# coil-control-module-v1.net
KiCad netlist of a schematic drawn in EAGLE
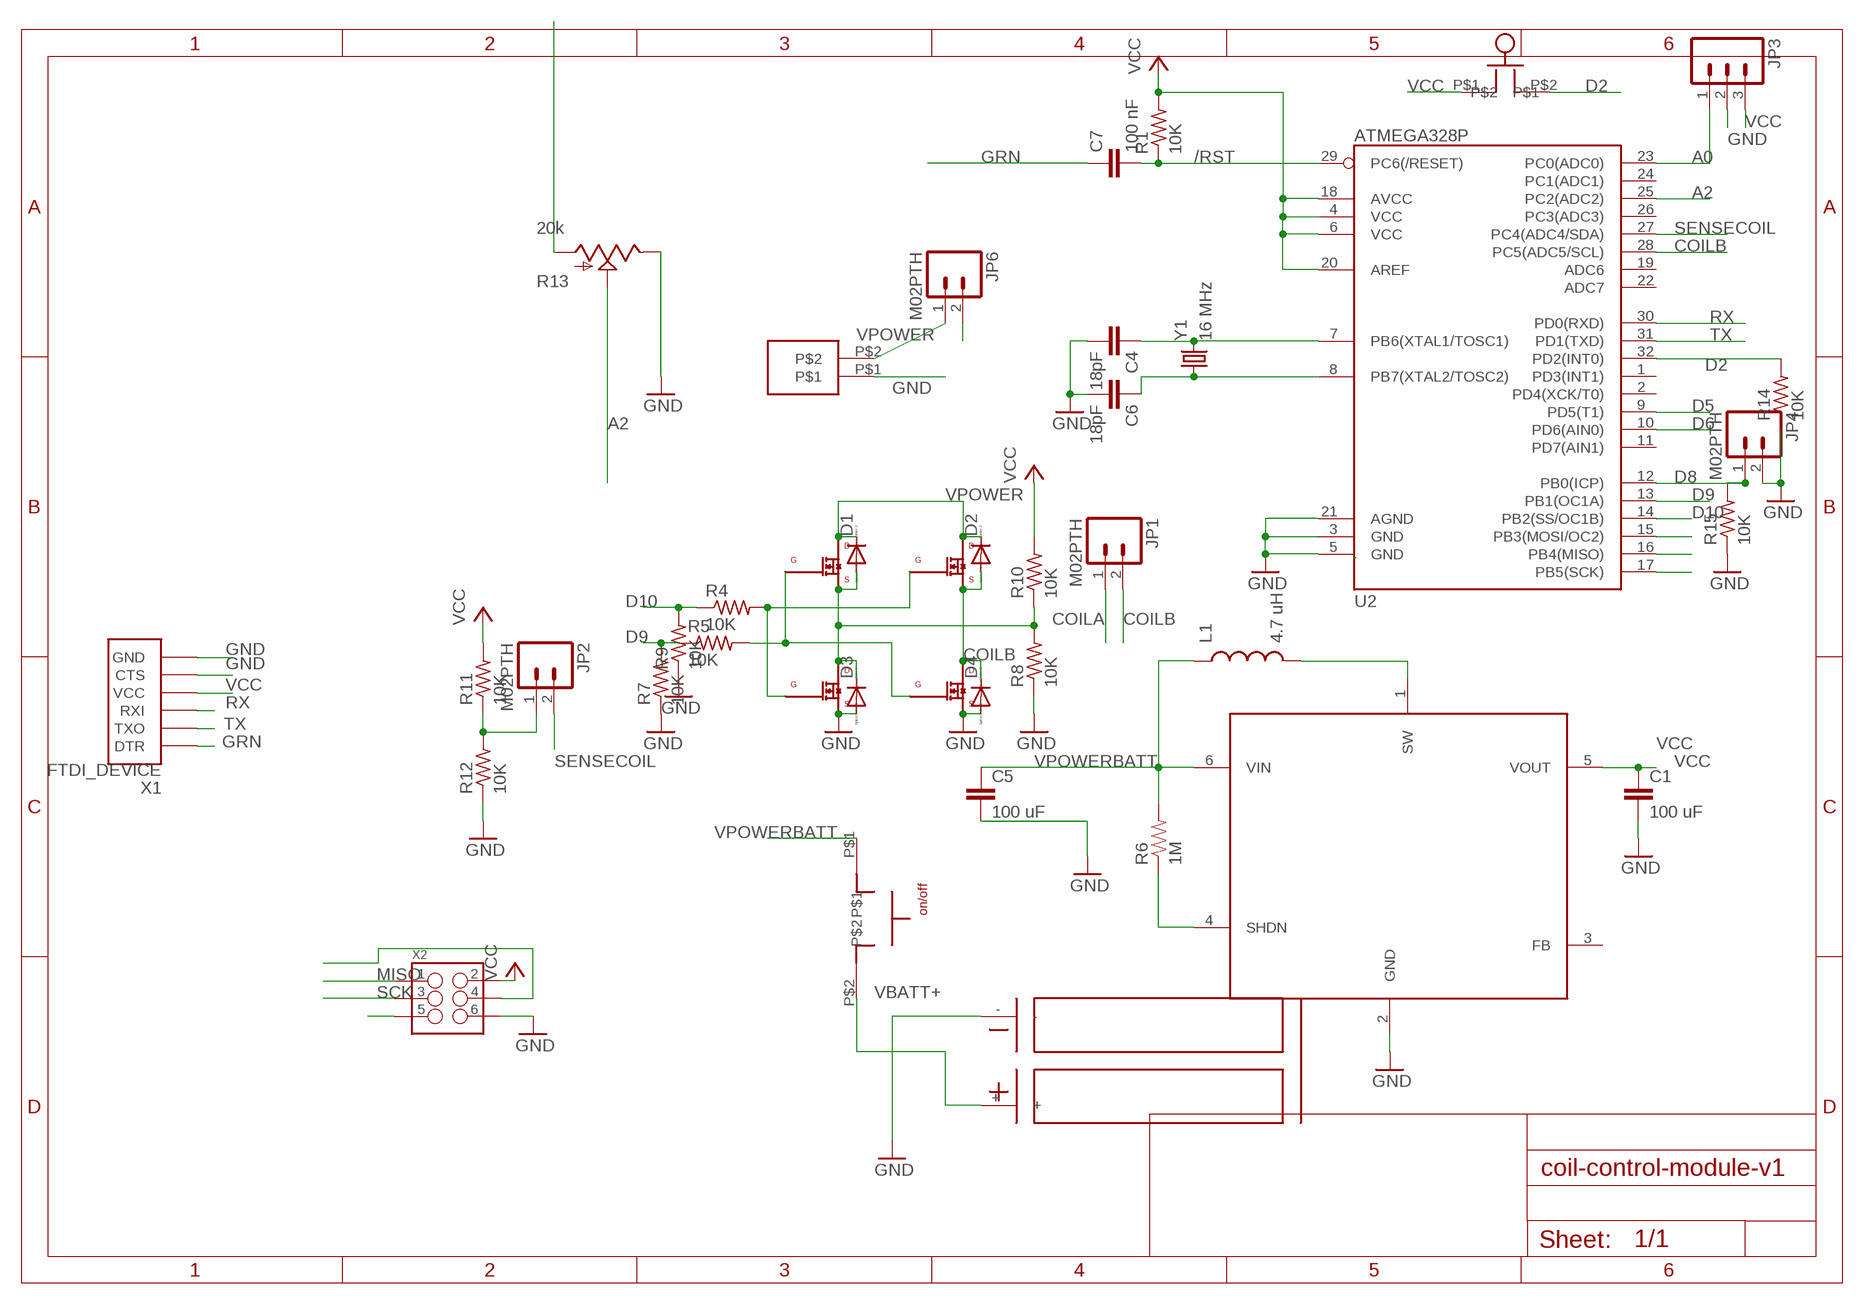
[diagram p0: schematic, sheet 1]

(export (version "E")
  (design (tool "Eeschema 10.0.6"))
  (components
    (comp (ref "C1")
      (value "100 uF")
      (footprint "eagle-import:1206")
      (libsource (lib "eagle-import") (part "CAP1206"))
    )
    (comp (ref "C4")
      (value "18pF")
      (footprint "eagle-import:C0603")
      (libsource (lib "eagle-import") (part "C-EUC0603"))
    )
    (comp (ref "C5")
      (value "100 uF")
      (footprint "eagle-import:1206")
      (libsource (lib "eagle-import") (part "CAP1206"))
    )
    (comp (ref "C6")
      (value "18pF")
      (footprint "eagle-import:C0603")
      (libsource (lib "eagle-import") (part "C-EUC0603"))
    )
    (comp (ref "C7")
      (value "100 nF")
      (footprint "eagle-import:0603-CAP")
      (libsource (lib "eagle-import") (part "SparkFun-Passives_CAP0603-CAP"))
    )
    (comp (ref "D1")
      (value "DIODE-DO-214AC")
      (footprint "eagle-import:DO-214AC")
      (libsource (lib "eagle-import") (part "DIODE-DO-214AC"))
    )
    (comp (ref "D2")
      (value "DIODE-DO-214AC")
      (footprint "eagle-import:DO-214AC")
      (libsource (lib "eagle-import") (part "DIODE-DO-214AC"))
    )
    (comp (ref "D3")
      (value "DIODE-DO-214AC")
      (footprint "eagle-import:DO-214AC")
      (libsource (lib "eagle-import") (part "DIODE-DO-214AC"))
    )
    (comp (ref "D4")
      (value "DIODE-DO-214AC")
      (footprint "eagle-import:DO-214AC")
      (libsource (lib "eagle-import") (part "DIODE-DO-214AC"))
    )
    (comp (ref "JP1")
      (value "M02PTH")
      (footprint "eagle-import:1X02")
      (libsource (lib "eagle-import") (part "M02PTH"))
    )
    (comp (ref "JP2")
      (value "M02PTH")
      (footprint "eagle-import:1X02")
      (libsource (lib "eagle-import") (part "M02PTH"))
    )
    (comp (ref "JP3")
      (value "M03PTH")
      (footprint "eagle-import:1X03")
      (libsource (lib "eagle-import") (part "M03PTH"))
    )
    (comp (ref "JP4")
      (value "M02PTH")
      (footprint "eagle-import:1X02")
      (libsource (lib "eagle-import") (part "M02PTH"))
    )
    (comp (ref "JP6")
      (value "M02PTH")
      (footprint "eagle-import:1X02")
      (libsource (lib "eagle-import") (part "M02PTH"))
    )
    (comp (ref "L1")
      (value "4.7 uH")
      (footprint "eagle-import:0805")
      (libsource (lib "eagle-import") (part "INDUCTOR0805"))
    )
    (comp (ref "R1")
      (value "10K")
      (footprint "eagle-import:R0603")
      (libsource (lib "eagle-import") (part "R-US_R0603"))
    )
    (comp (ref "R4")
      (value "10K")
      (footprint "eagle-import:R0603")
      (libsource (lib "eagle-import") (part "R-US_R0603"))
    )
    (comp (ref "R5")
      (value "10K")
      (footprint "eagle-import:R0603")
      (libsource (lib "eagle-import") (part "R-US_R0603"))
    )
    (comp (ref "R6")
      (value "1M")
      (footprint "eagle-import:0805")
      (libsource (lib "eagle-import") (part "RESISTOR0805-RES"))
    )
    (comp (ref "R7")
      (value "10K")
      (footprint "eagle-import:R0603")
      (libsource (lib "eagle-import") (part "R-US_R0603"))
    )
    (comp (ref "R8")
      (value "10K")
      (footprint "eagle-import:R0603")
      (libsource (lib "eagle-import") (part "R-US_R0603"))
    )
    (comp (ref "R9")
      (value "10K")
      (footprint "eagle-import:R0603")
      (libsource (lib "eagle-import") (part "R-US_R0603"))
    )
    (comp (ref "R10")
      (value "10K")
      (footprint "eagle-import:R0603")
      (libsource (lib "eagle-import") (part "R-US_R0603"))
    )
    (comp (ref "R11")
      (value "10K")
      (footprint "eagle-import:R0603")
      (libsource (lib "eagle-import") (part "R-US_R0603"))
    )
    (comp (ref "R12")
      (value "10K")
      (footprint "eagle-import:R0603")
      (libsource (lib "eagle-import") (part "R-US_R0603"))
    )
    (comp (ref "R13")
      (value "20k")
      (footprint "eagle-import:ALPS_POT_KIT")
      (libsource (lib "eagle-import") (part "POTALPS-KIT"))
    )
    (comp (ref "R14")
      (value "10K")
      (footprint "eagle-import:R0603")
      (libsource (lib "eagle-import") (part "R-US_R0603"))
    )
    (comp (ref "R15")
      (value "10K")
      (footprint "eagle-import:R0603")
      (libsource (lib "eagle-import") (part "R-US_R0603"))
    )
    (comp (ref "U$1")
      (value "IRLML0060")
      (footprint "eagle-import:SOT-23")
      (libsource (lib "eagle-import") (part "IRLML0060"))
    )
    (comp (ref "U$2")
      (value "IRLML0060")
      (footprint "eagle-import:SOT-23")
      (libsource (lib "eagle-import") (part "IRLML0060"))
    )
    (comp (ref "U$3")
      (value "IRLML0060")
      (footprint "eagle-import:SOT-23")
      (libsource (lib "eagle-import") (part "IRLML0060"))
    )
    (comp (ref "U$4")
      (value "AA-DOUBLE-UPSIDE-DOWN")
      (footprint "eagle-import:AA-DOUBLE-UPSIDE-DOWN")
      (libsource (lib "eagle-import") (part "AA-DOUBLE-UPSIDE-DOWN"))
    )
    (comp (ref "U$5")
      (value "CW182-ND")
      (footprint "eagle-import:CW182-ND")
      (libsource (lib "eagle-import") (part "CW182-ND"))
    )
    (comp (ref "U$6")
      (value "IRLML0060")
      (footprint "eagle-import:SOT-23")
      (libsource (lib "eagle-import") (part "IRLML0060"))
    )
    (comp (ref "U$7")
      (value "BUTTON")
      (footprint "eagle-import:BUTTON")
      (libsource (lib "eagle-import") (part "BUTTON"))
    )
    (comp (ref "U$8")
      (value "SPRING-TERMINAL")
      (footprint "eagle-import:SPRING-TERMINAL")
      (libsource (lib "eagle-import") (part "SPRING-TERMINAL"))
    )
    (comp (ref "U1")
      (value "AAT1217")
      (footprint "eagle-import:SSOT23-6")
      (libsource (lib "eagle-import") (part "AAT1217"))
    )
    (comp (ref "U2")
      (value "ATMEGA328P")
      (footprint "eagle-import:TQFP32-08")
      (libsource (lib "eagle-import") (part "ATMEGA328_SMT"))
    )
    (comp (ref "X1")
      (value "FTDI_DEVICE")
      (footprint "eagle-import:FTDI_DEVICE_SIDE")
      (libsource (lib "eagle-import") (part "FTDI_DEVICE"))
    )
    (comp (ref "X2")
      (value "M03X2NO_SILK")
      (footprint "eagle-import:2X3-NS")
      (libsource (lib "eagle-import") (part "M03X2NO_SILK"))
    )
    (comp (ref "Y1")
      (value "16 MHz")
      (footprint "eagle-import:CRYSTAL-SMD-5X3")
      (libsource (lib "eagle-import") (part "CRYSTAL5X3"))
    )
  )
  (nets
    (net (code "1") (name "/A0") (class "Default")
      (node (ref "JP3") (pin "1") (pinfunction "1_1") (pintype "passive"))
      (node (ref "U2") (pin "23") (pinfunction "PC0(ADC0)_23") (pintype "bidirectional"))
    )
    (net (code "2") (name "/A2") (class "Default")
      (node (ref "R13") (pin "P$2") (pinfunction "S_P$2") (pintype "passive"))
      (node (ref "U2") (pin "25") (pinfunction "PC2(ADC2)_25") (pintype "bidirectional"))
    )
    (net (code "3") (name "/COILA") (class "Default")
      (node (ref "D1") (pin "A") (pinfunction "A_A") (pintype "passive"))
      (node (ref "D3") (pin "C") (pinfunction "C_C") (pintype "passive"))
      (node (ref "JP1") (pin "1") (pinfunction "1_1") (pintype "passive"))
      (node (ref "R10") (pin "1") (pinfunction "1_1") (pintype "passive"))
      (node (ref "R8") (pin "2") (pinfunction "2_2") (pintype "passive"))
      (node (ref "U$3") (pin "2") (pinfunction "SOURCE_2") (pintype "bidirectional"))
      (node (ref "U$6") (pin "3") (pinfunction "DRAIN_3") (pintype "bidirectional"))
    )
    (net (code "4") (name "/COILB") (class "Default")
      (node (ref "D2") (pin "A") (pinfunction "A_A") (pintype "passive"))
      (node (ref "D4") (pin "C") (pinfunction "C_C") (pintype "passive"))
      (node (ref "JP1") (pin "2") (pinfunction "2_2") (pintype "passive"))
      (node (ref "U$1") (pin "3") (pinfunction "DRAIN_3") (pintype "bidirectional"))
      (node (ref "U$2") (pin "2") (pinfunction "SOURCE_2") (pintype "bidirectional"))
      (node (ref "U2") (pin "28") (pinfunction "PC5(ADC5/SCL)_28") (pintype "bidirectional"))
    )
    (net (code "5") (name "/D2") (class "Default")
      (node (ref "R14") (pin "2") (pinfunction "2_2") (pintype "passive"))
      (node (ref "U$7") (pin "P$2") (pinfunction "P$2_P$2") (pintype "bidirectional"))
      (node (ref "U2") (pin "32") (pinfunction "PD2(INT0)_32") (pintype "bidirectional"))
    )
    (net (code "6") (name "/D5") (class "Default")
      (node (ref "U2") (pin "9") (pinfunction "PD5(T1)_9") (pintype "bidirectional"))
    )
    (net (code "7") (name "/D6") (class "Default")
      (node (ref "U2") (pin "10") (pinfunction "PD6(AIN0)_10") (pintype "bidirectional"))
    )
    (net (code "8") (name "/D8") (class "Default")
      (node (ref "JP4") (pin "1") (pinfunction "1_1") (pintype "passive"))
      (node (ref "R15") (pin "2") (pinfunction "2_2") (pintype "passive"))
      (node (ref "U2") (pin "12") (pinfunction "PB0(ICP)_12") (pintype "bidirectional"))
    )
    (net (code "9") (name "/D9") (class "Default")
      (node (ref "R5") (pin "1") (pinfunction "1_1") (pintype "passive"))
      (node (ref "R7") (pin "2") (pinfunction "2_2") (pintype "passive"))
      (node (ref "U2") (pin "13") (pinfunction "PB1(OC1A)_13") (pintype "bidirectional"))
    )
    (net (code "10") (name "/D10") (class "Default")
      (node (ref "R4") (pin "1") (pinfunction "1_1") (pintype "passive"))
      (node (ref "R9") (pin "2") (pinfunction "2_2") (pintype "passive"))
      (node (ref "U2") (pin "14") (pinfunction "PB2(SS/OC1B)_14") (pintype "bidirectional"))
    )
    (net (code "11") (name "/GRN") (class "Default")
      (node (ref "C7") (pin "1") (pinfunction "1_1") (pintype "passive"))
      (node (ref "X1") (pin "P$1") (pinfunction "DTR_P$1") (pintype "bidirectional"))
    )
    (net (code "12") (name "/MISO") (class "Default")
      (node (ref "U2") (pin "16") (pinfunction "PB4(MISO)_16") (pintype "bidirectional"))
      (node (ref "X2") (pin "1") (pinfunction "1_1") (pintype "bidirectional"))
    )
    (net (code "13") (name "/MOSI") (class "Default")
      (node (ref "U2") (pin "15") (pinfunction "PB3(MOSI/OC2)_15") (pintype "bidirectional"))
      (node (ref "X2") (pin "4") (pinfunction "4_4") (pintype "bidirectional"))
    )
    (net (code "14") (name "/RX") (class "Default")
      (node (ref "U2") (pin "30") (pinfunction "PD0(RXD)_30") (pintype "bidirectional"))
      (node (ref "X1") (pin "P$3") (pinfunction "RXI_P$3") (pintype "bidirectional"))
    )
    (net (code "15") (name "/SCK") (class "Default")
      (node (ref "U2") (pin "17") (pinfunction "PB5(SCK)_17") (pintype "bidirectional"))
      (node (ref "X2") (pin "3") (pinfunction "3_3") (pintype "bidirectional"))
    )
    (net (code "16") (name "/SENSECOIL") (class "Default")
      (node (ref "JP2") (pin "2") (pinfunction "2_2") (pintype "passive"))
      (node (ref "U2") (pin "27") (pinfunction "PC4(ADC4/SDA)_27") (pintype "bidirectional"))
    )
    (net (code "17") (name "/TX") (class "Default")
      (node (ref "U2") (pin "31") (pinfunction "PD1(TXD)_31") (pintype "bidirectional"))
      (node (ref "X1") (pin "P$2") (pinfunction "TXO_P$2") (pintype "bidirectional"))
    )
    (net (code "18") (name "/VBATT+") (class "Default")
      (node (ref "U$4") (pin "+") (pinfunction "+_+") (pintype "bidirectional"))
      (node (ref "U$5") (pin "P$2") (pinfunction "P$2_P$2") (pintype "bidirectional"))
    )
    (net (code "19") (name "/VPOWER") (class "Default")
      (node (ref "D1") (pin "C") (pinfunction "C_C") (pintype "passive"))
      (node (ref "D2") (pin "C") (pinfunction "C_C") (pintype "passive"))
      (node (ref "JP6") (pin "1") (pinfunction "1_1") (pintype "passive"))
      (node (ref "U$2") (pin "3") (pinfunction "DRAIN_3") (pintype "bidirectional"))
      (node (ref "U$3") (pin "3") (pinfunction "DRAIN_3") (pintype "bidirectional"))
      (node (ref "U$8") (pin "P$2") (pinfunction "P$2_P$2") (pintype "bidirectional"))
    )
    (net (code "20") (name "/VPOWERBATT") (class "Default")
      (node (ref "C5") (pin "1") (pinfunction "1_1") (pintype "passive"))
      (node (ref "JP6") (pin "2") (pinfunction "2_2") (pintype "passive"))
      (node (ref "L1") (pin "1") (pinfunction "1_1") (pintype "passive"))
      (node (ref "R6") (pin "2") (pinfunction "2_2") (pintype "passive"))
      (node (ref "U$5") (pin "P$1") (pinfunction "P$1_P$1") (pintype "bidirectional"))
      (node (ref "U1") (pin "6") (pinfunction "VIN_6") (pintype "bidirectional"))
    )
    (net (code "21") (name "/{slash}RST") (class "Default")
      (node (ref "C7") (pin "2") (pinfunction "2_2") (pintype "passive"))
      (node (ref "R1") (pin "1") (pinfunction "1_1") (pintype "passive"))
      (node (ref "U2") (pin "29") (pinfunction "PC6(/RESET)_29") (pintype "bidirectional"))
      (node (ref "X2") (pin "5") (pinfunction "5_5") (pintype "bidirectional"))
    )
    (net (code "22") (name "GND") (class "Default")
      (node (ref "C1") (pin "2") (pinfunction "2_2") (pintype "passive"))
      (node (ref "C4") (pin "2") (pinfunction "2_2") (pintype "passive"))
      (node (ref "C5") (pin "2") (pinfunction "2_2") (pintype "passive"))
      (node (ref "C6") (pin "2") (pinfunction "2_2") (pintype "passive"))
      (node (ref "D3") (pin "A") (pinfunction "A_A") (pintype "passive"))
      (node (ref "D4") (pin "A") (pinfunction "A_A") (pintype "passive"))
      (node (ref "JP3") (pin "2") (pinfunction "2_2") (pintype "passive"))
      (node (ref "JP4") (pin "2") (pinfunction "2_2") (pintype "passive"))
      (node (ref "R12") (pin "1") (pinfunction "1_1") (pintype "passive"))
      (node (ref "R13") (pin "P$1") (pinfunction "E_P$1") (pintype "passive"))
      (node (ref "R14") (pin "1") (pinfunction "1_1") (pintype "passive"))
      (node (ref "R15") (pin "1") (pinfunction "1_1") (pintype "passive"))
      (node (ref "R7") (pin "1") (pinfunction "1_1") (pintype "passive"))
      (node (ref "R8") (pin "1") (pinfunction "1_1") (pintype "passive"))
      (node (ref "R9") (pin "1") (pinfunction "1_1") (pintype "passive"))
      (node (ref "U$1") (pin "2") (pinfunction "SOURCE_2") (pintype "bidirectional"))
      (node (ref "U$4") (pin "-") (pinfunction "-_-") (pintype "bidirectional"))
      (node (ref "U$6") (pin "2") (pinfunction "SOURCE_2") (pintype "bidirectional"))
      (node (ref "U$8") (pin "P$1") (pinfunction "P$1_P$1") (pintype "bidirectional"))
      (node (ref "U1") (pin "2") (pinfunction "GND_2") (pintype "bidirectional"))
      (node (ref "U2") (pin "21") (pinfunction "AGND_21") (pintype "bidirectional"))
      (node (ref "U2") (pin "3") (pinfunction "GND_3") (pintype "bidirectional"))
      (node (ref "U2") (pin "5") (pinfunction "GND_5") (pintype "bidirectional"))
      (node (ref "X1") (pin "P$5") (pinfunction "CTS_P$5") (pintype "bidirectional"))
      (node (ref "X1") (pin "P$6") (pinfunction "GND_P$6") (pintype "bidirectional"))
      (node (ref "X2") (pin "6") (pinfunction "6_6") (pintype "bidirectional"))
    )
    (net (code "23") (name "Net-(JP2-Pad1)") (class "Default")
      (node (ref "JP2") (pin "1") (pinfunction "1_1") (pintype "passive"))
      (node (ref "R11") (pin "1") (pinfunction "1_1") (pintype "passive"))
      (node (ref "R12") (pin "2") (pinfunction "2_2") (pintype "passive"))
    )
    (net (code "24") (name "Net-(U$1-GATE)") (class "Default")
      (node (ref "R5") (pin "2") (pinfunction "2_2") (pintype "passive"))
      (node (ref "U$1") (pin "1") (pinfunction "GATE_1") (pintype "bidirectional"))
      (node (ref "U$3") (pin "1") (pinfunction "GATE_1") (pintype "bidirectional"))
    )
    (net (code "25") (name "Net-(U$2-GATE)") (class "Default")
      (node (ref "R4") (pin "2") (pinfunction "2_2") (pintype "passive"))
      (node (ref "U$2") (pin "1") (pinfunction "GATE_1") (pintype "bidirectional"))
      (node (ref "U$6") (pin "1") (pinfunction "GATE_1") (pintype "bidirectional"))
    )
    (net (code "26") (name "Net-(U1-SHDN)") (class "Default")
      (node (ref "R6") (pin "1") (pinfunction "1_1") (pintype "passive"))
      (node (ref "U1") (pin "4") (pinfunction "SHDN_4") (pintype "bidirectional"))
    )
    (net (code "27") (name "Net-(U1-SW)") (class "Default")
      (node (ref "L1") (pin "2") (pinfunction "2_2") (pintype "passive"))
      (node (ref "U1") (pin "1") (pinfunction "SW_1") (pintype "bidirectional"))
    )
    (net (code "28") (name "Net-(U2-PB6(XTAL1{slash}TOSC1))") (class "Default")
      (node (ref "C4") (pin "1") (pinfunction "1_1") (pintype "passive"))
      (node (ref "U2") (pin "7") (pinfunction "PB6(XTAL1/TOSC1)_7") (pintype "bidirectional"))
      (node (ref "Y1") (pin "3") (pinfunction "2_3") (pintype "passive"))
    )
    (net (code "29") (name "Net-(U2-PB7(XTAL2{slash}TOSC2))") (class "Default")
      (node (ref "C6") (pin "1") (pinfunction "1_1") (pintype "passive"))
      (node (ref "U2") (pin "8") (pinfunction "PB7(XTAL2/TOSC2)_8") (pintype "bidirectional"))
      (node (ref "Y1") (pin "1") (pinfunction "1_1") (pintype "passive"))
    )
    (net (code "30") (name "VCC") (class "Default")
      (node (ref "C1") (pin "1") (pinfunction "1_1") (pintype "passive"))
      (node (ref "JP3") (pin "3") (pinfunction "3_3") (pintype "passive"))
      (node (ref "R1") (pin "2") (pinfunction "2_2") (pintype "passive"))
      (node (ref "R10") (pin "2") (pinfunction "2_2") (pintype "passive"))
      (node (ref "R11") (pin "2") (pinfunction "2_2") (pintype "passive"))
      (node (ref "R13") (pin "P$3") (pinfunction "A_P$3") (pintype "passive"))
      (node (ref "U$7") (pin "P$1") (pinfunction "P$1_P$1") (pintype "bidirectional"))
      (node (ref "U1") (pin "5") (pinfunction "VOUT_5") (pintype "bidirectional"))
      (node (ref "U2") (pin "18") (pinfunction "AVCC_18") (pintype "bidirectional"))
      (node (ref "U2") (pin "20") (pinfunction "AREF_20") (pintype "bidirectional"))
      (node (ref "U2") (pin "4") (pinfunction "VCC_4") (pintype "bidirectional"))
      (node (ref "U2") (pin "6") (pinfunction "VCC_6") (pintype "bidirectional"))
      (node (ref "X1") (pin "P$4") (pinfunction "VCC_P$4") (pintype "bidirectional"))
      (node (ref "X2") (pin "2") (pinfunction "2_2") (pintype "bidirectional"))
    )
    (net (code "31") (name "unconnected-(U1-FB-Pad3)") (class "Default")
      (node (ref "U1") (pin "3") (pinfunction "FB_3") (pintype "bidirectional"))
    )
    (net (code "32") (name "unconnected-(U2-ADC6-Pad19)") (class "Default")
      (node (ref "U2") (pin "19") (pinfunction "ADC6_19") (pintype "bidirectional"))
    )
    (net (code "33") (name "unconnected-(U2-ADC7-Pad22)") (class "Default")
      (node (ref "U2") (pin "22") (pinfunction "ADC7_22") (pintype "bidirectional"))
    )
    (net (code "34") (name "unconnected-(U2-PC1(ADC1)-Pad24)") (class "Default")
      (node (ref "U2") (pin "24") (pinfunction "PC1(ADC1)_24") (pintype "bidirectional"))
    )
    (net (code "35") (name "unconnected-(U2-PC3(ADC3)-Pad26)") (class "Default")
      (node (ref "U2") (pin "26") (pinfunction "PC3(ADC3)_26") (pintype "bidirectional"))
    )
    (net (code "36") (name "unconnected-(U2-PD3(INT1)-Pad1)") (class "Default")
      (node (ref "U2") (pin "1") (pinfunction "PD3(INT1)_1") (pintype "bidirectional"))
    )
    (net (code "37") (name "unconnected-(U2-PD4(XCK{slash}T0)-Pad2)") (class "Default")
      (node (ref "U2") (pin "2") (pinfunction "PD4(XCK/T0)_2") (pintype "bidirectional"))
    )
    (net (code "38") (name "unconnected-(U2-PD7(AIN1)-Pad11)") (class "Default")
      (node (ref "U2") (pin "11") (pinfunction "PD7(AIN1)_11") (pintype "bidirectional"))
    )
  )
)
